# L298_driver.net
KiCad netlist of a schematic drawn in EAGLE
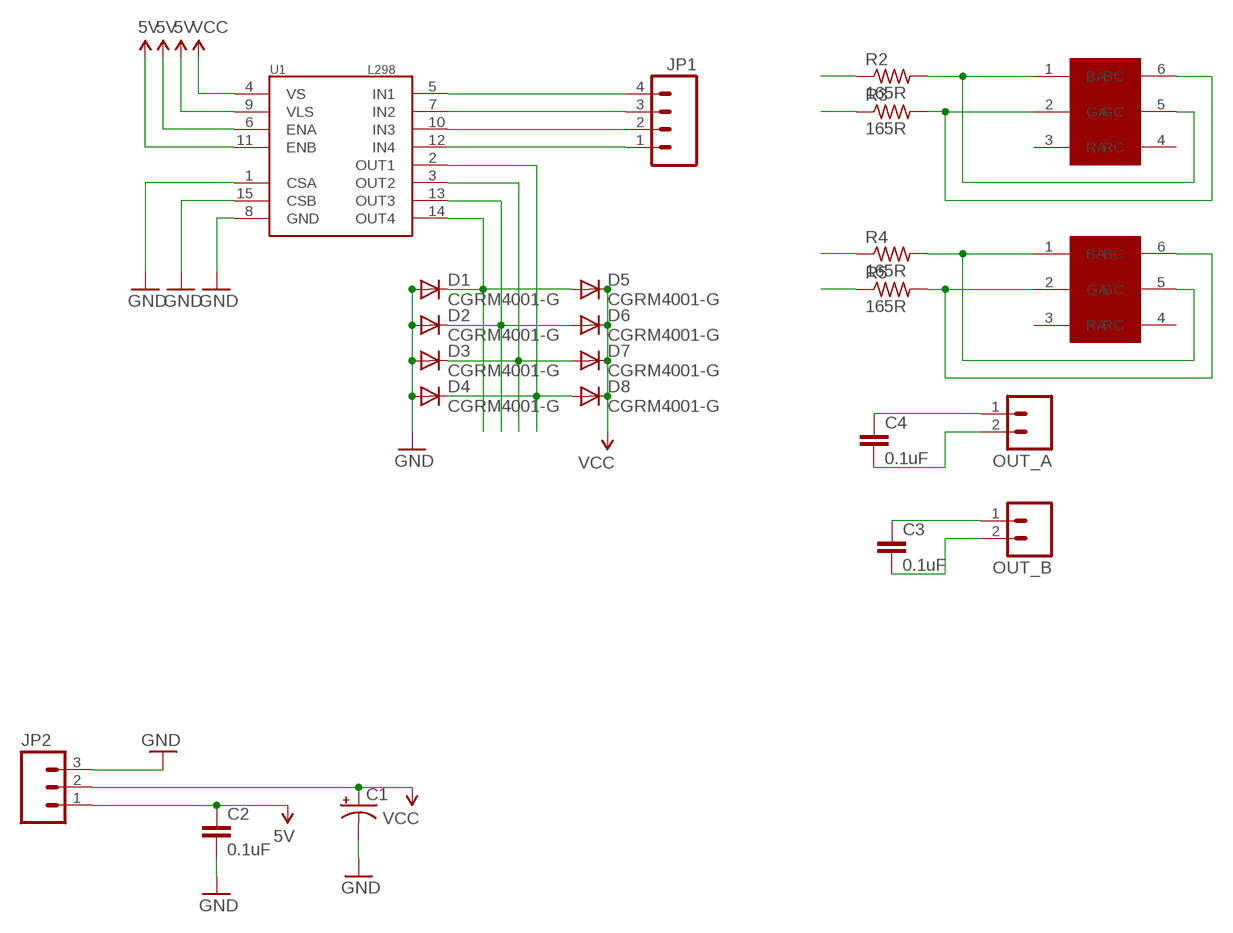
[diagram p0: schematic, sheet 1]

(export (version "E")
  (design (tool "Eeschema 10.0.6"))
  (components
    (comp (ref "C1")
      (value "CPOL-USTT5D11L")
      (footprint "eagle-import:TT5D11L")
      (libsource (lib "eagle-import") (part "CPOL-USTT5D11L"))
    )
    (comp (ref "C2")
      (value "0.1uF")
      (footprint "eagle-import:0402-CAP")
      (libsource (lib "eagle-import") (part "CAP0402-CAP"))
    )
    (comp (ref "C3")
      (value "0.1uF")
      (footprint "eagle-import:0402-CAP")
      (libsource (lib "eagle-import") (part "CAP0402-CAP"))
    )
    (comp (ref "C4")
      (value "0.1uF")
      (footprint "eagle-import:0402-CAP")
      (libsource (lib "eagle-import") (part "CAP0402-CAP"))
    )
    (comp (ref "D1")
      (value "CGRM4001-G")
      (footprint "eagle-import:SOD-123_MINI-SMA")
      (libsource (lib "eagle-import") (part "CGRM400-G1"))
    )
    (comp (ref "D2")
      (value "CGRM4001-G")
      (footprint "eagle-import:SOD-123_MINI-SMA")
      (libsource (lib "eagle-import") (part "CGRM400-G1"))
    )
    (comp (ref "D3")
      (value "CGRM4001-G")
      (footprint "eagle-import:SOD-123_MINI-SMA")
      (libsource (lib "eagle-import") (part "CGRM400-G1"))
    )
    (comp (ref "D4")
      (value "CGRM4001-G")
      (footprint "eagle-import:SOD-123_MINI-SMA")
      (libsource (lib "eagle-import") (part "CGRM400-G1"))
    )
    (comp (ref "D5")
      (value "CGRM4001-G")
      (footprint "eagle-import:SOD-123_MINI-SMA")
      (libsource (lib "eagle-import") (part "CGRM400-G1"))
    )
    (comp (ref "D6")
      (value "CGRM4001-G")
      (footprint "eagle-import:SOD-123_MINI-SMA")
      (libsource (lib "eagle-import") (part "CGRM400-G1"))
    )
    (comp (ref "D7")
      (value "CGRM4001-G")
      (footprint "eagle-import:SOD-123_MINI-SMA")
      (libsource (lib "eagle-import") (part "CGRM400-G1"))
    )
    (comp (ref "D8")
      (value "CGRM4001-G")
      (footprint "eagle-import:SOD-123_MINI-SMA")
      (libsource (lib "eagle-import") (part "CGRM400-G1"))
    )
    (comp (ref "JP1")
      (value "M04POLAR")
      (footprint "eagle-import:MOLEX-1X4")
      (libsource (lib "eagle-import") (part "M04POLAR"))
    )
    (comp (ref "JP2")
      (value "M03-SCREW-5MM")
      (footprint "eagle-import:SCREWTERMINAL-5MM-3")
      (libsource (lib "eagle-import") (part "M03-SCREW-5MM"))
    )
    (comp (ref "LED_A")
      (value "LRTB_R98G")
      (footprint "eagle-import:6-SMD")
      (libsource (lib "eagle-import") (part "LRTB_R98G"))
    )
    (comp (ref "LED_B")
      (value "LRTB_R98G")
      (footprint "eagle-import:6-SMD")
      (libsource (lib "eagle-import") (part "LRTB_R98G"))
    )
    (comp (ref "OUT_A")
      (value "M025MM")
      (footprint "eagle-import:SCREWTERMINAL-5MM-2")
      (libsource (lib "eagle-import") (part "M025MM"))
    )
    (comp (ref "OUT_B")
      (value "M025MM")
      (footprint "eagle-import:SCREWTERMINAL-5MM-2")
      (libsource (lib "eagle-import") (part "M025MM"))
    )
    (comp (ref "R2")
      (value "165R")
      (footprint "eagle-import:R0402")
      (libsource (lib "eagle-import") (part "R-US_R0402"))
    )
    (comp (ref "R3")
      (value "165R")
      (footprint "eagle-import:R0402")
      (libsource (lib "eagle-import") (part "R-US_R0402"))
    )
    (comp (ref "R4")
      (value "165R")
      (footprint "eagle-import:R0402")
      (libsource (lib "eagle-import") (part "R-US_R0402"))
    )
    (comp (ref "R5")
      (value "165R")
      (footprint "eagle-import:R0402")
      (libsource (lib "eagle-import") (part "R-US_R0402"))
    )
    (comp (ref "U1")
      (value "L298")
      (footprint "eagle-import:MULTIWATT15")
      (libsource (lib "eagle-import") (part "L298"))
    )
  )
  (nets
    (net (code "1") (name "/IN1") (class "Default")
      (node (ref "JP1") (pin "4") (pinfunction "4_4") (pintype "passive"))
      (node (ref "R2") (pin "1") (pinfunction "1_1") (pintype "passive"))
      (node (ref "U1") (pin "5") (pinfunction "IN1_5") (pintype "bidirectional"))
    )
    (net (code "2") (name "/IN2") (class "Default")
      (node (ref "JP1") (pin "3") (pinfunction "3_3") (pintype "passive"))
      (node (ref "R3") (pin "1") (pinfunction "1_1") (pintype "passive"))
      (node (ref "U1") (pin "7") (pinfunction "IN2_7") (pintype "bidirectional"))
    )
    (net (code "3") (name "/IN3") (class "Default")
      (node (ref "JP1") (pin "2") (pinfunction "2_2") (pintype "passive"))
      (node (ref "R4") (pin "1") (pinfunction "1_1") (pintype "passive"))
      (node (ref "U1") (pin "10") (pinfunction "IN3_10") (pintype "bidirectional"))
    )
    (net (code "4") (name "/IN4") (class "Default")
      (node (ref "JP1") (pin "1") (pinfunction "1_1") (pintype "passive"))
      (node (ref "R5") (pin "1") (pinfunction "1_1") (pintype "passive"))
      (node (ref "U1") (pin "12") (pinfunction "IN4_12") (pintype "bidirectional"))
    )
    (net (code "5") (name "/OUT1") (class "Default")
      (node (ref "C4") (pin "1") (pinfunction "1_1") (pintype "passive"))
      (node (ref "D4") (pin "C") (pinfunction "C_C") (pintype "passive"))
      (node (ref "D8") (pin "A") (pinfunction "A_A") (pintype "passive"))
      (node (ref "OUT_A") (pin "1") (pinfunction "1_1") (pintype "passive"))
      (node (ref "U1") (pin "2") (pinfunction "OUT1_2") (pintype "bidirectional"))
    )
    (net (code "6") (name "/OUT2") (class "Default")
      (node (ref "C4") (pin "2") (pinfunction "2_2") (pintype "passive"))
      (node (ref "D3") (pin "C") (pinfunction "C_C") (pintype "passive"))
      (node (ref "D7") (pin "A") (pinfunction "A_A") (pintype "passive"))
      (node (ref "OUT_A") (pin "2") (pinfunction "2_2") (pintype "passive"))
      (node (ref "U1") (pin "3") (pinfunction "OUT2_3") (pintype "bidirectional"))
    )
    (net (code "7") (name "/OUT3") (class "Default")
      (node (ref "C3") (pin "1") (pinfunction "1_1") (pintype "passive"))
      (node (ref "D2") (pin "C") (pinfunction "C_C") (pintype "passive"))
      (node (ref "D6") (pin "A") (pinfunction "A_A") (pintype "passive"))
      (node (ref "OUT_B") (pin "1") (pinfunction "1_1") (pintype "passive"))
      (node (ref "U1") (pin "13") (pinfunction "OUT3_13") (pintype "bidirectional"))
    )
    (net (code "8") (name "/OUT4") (class "Default")
      (node (ref "C3") (pin "2") (pinfunction "2_2") (pintype "passive"))
      (node (ref "D1") (pin "C") (pinfunction "C_C") (pintype "passive"))
      (node (ref "D5") (pin "A") (pinfunction "A_A") (pintype "passive"))
      (node (ref "OUT_B") (pin "2") (pinfunction "2_2") (pintype "passive"))
      (node (ref "U1") (pin "14") (pinfunction "OUT4_14") (pintype "bidirectional"))
    )
    (net (code "9") (name "5V") (class "Default")
      (node (ref "C2") (pin "1") (pinfunction "1_1") (pintype "passive"))
      (node (ref "JP2") (pin "1") (pinfunction "1_1") (pintype "passive"))
      (node (ref "U1") (pin "11") (pinfunction "ENB_11") (pintype "bidirectional"))
      (node (ref "U1") (pin "6") (pinfunction "ENA_6") (pintype "bidirectional"))
      (node (ref "U1") (pin "9") (pinfunction "VLS_9") (pintype "bidirectional"))
    )
    (net (code "10") (name "GND") (class "Default")
      (node (ref "C1") (pin "-") (pinfunction "-_-") (pintype "passive"))
      (node (ref "C2") (pin "2") (pinfunction "2_2") (pintype "passive"))
      (node (ref "D1") (pin "A") (pinfunction "A_A") (pintype "passive"))
      (node (ref "D2") (pin "A") (pinfunction "A_A") (pintype "passive"))
      (node (ref "D3") (pin "A") (pinfunction "A_A") (pintype "passive"))
      (node (ref "D4") (pin "A") (pinfunction "A_A") (pintype "passive"))
      (node (ref "JP2") (pin "3") (pinfunction "3_3") (pintype "passive"))
      (node (ref "U1") (pin "1") (pinfunction "CSA_1") (pintype "bidirectional"))
      (node (ref "U1") (pin "15") (pinfunction "CSB_15") (pintype "bidirectional"))
      (node (ref "U1") (pin "8") (pinfunction "GND_8") (pintype "bidirectional"))
    )
    (net (code "11") (name "Net-(LED_A-BA)") (class "Default")
      (node (ref "LED_A") (pin "1") (pinfunction "BA_1") (pintype "bidirectional"))
      (node (ref "LED_A") (pin "5") (pinfunction "GC_5") (pintype "bidirectional"))
      (node (ref "R2") (pin "2") (pinfunction "2_2") (pintype "passive"))
    )
    (net (code "12") (name "Net-(LED_A-BC)") (class "Default")
      (node (ref "LED_A") (pin "2") (pinfunction "GA_2") (pintype "bidirectional"))
      (node (ref "LED_A") (pin "6") (pinfunction "BC_6") (pintype "bidirectional"))
      (node (ref "R3") (pin "2") (pinfunction "2_2") (pintype "passive"))
    )
    (net (code "13") (name "Net-(LED_B-BA)") (class "Default")
      (node (ref "LED_B") (pin "1") (pinfunction "BA_1") (pintype "bidirectional"))
      (node (ref "LED_B") (pin "5") (pinfunction "GC_5") (pintype "bidirectional"))
      (node (ref "R4") (pin "2") (pinfunction "2_2") (pintype "passive"))
    )
    (net (code "14") (name "Net-(LED_B-BC)") (class "Default")
      (node (ref "LED_B") (pin "2") (pinfunction "GA_2") (pintype "bidirectional"))
      (node (ref "LED_B") (pin "6") (pinfunction "BC_6") (pintype "bidirectional"))
      (node (ref "R5") (pin "2") (pinfunction "2_2") (pintype "passive"))
    )
    (net (code "15") (name "VCC") (class "Default")
      (node (ref "C1") (pin "+") (pinfunction "+_+") (pintype "passive"))
      (node (ref "D5") (pin "C") (pinfunction "C_C") (pintype "passive"))
      (node (ref "D6") (pin "C") (pinfunction "C_C") (pintype "passive"))
      (node (ref "D7") (pin "C") (pinfunction "C_C") (pintype "passive"))
      (node (ref "D8") (pin "C") (pinfunction "C_C") (pintype "passive"))
      (node (ref "JP2") (pin "2") (pinfunction "2_2") (pintype "passive"))
      (node (ref "U1") (pin "4") (pinfunction "VS_4") (pintype "bidirectional"))
    )
    (net (code "16") (name "unconnected-(LED_A-RA-Pad3)") (class "Default")
      (node (ref "LED_A") (pin "3") (pinfunction "RA_3") (pintype "bidirectional"))
    )
    (net (code "17") (name "unconnected-(LED_A-RC-Pad4)") (class "Default")
      (node (ref "LED_A") (pin "4") (pinfunction "RC_4") (pintype "bidirectional"))
    )
    (net (code "18") (name "unconnected-(LED_B-RA-Pad3)") (class "Default")
      (node (ref "LED_B") (pin "3") (pinfunction "RA_3") (pintype "bidirectional"))
    )
    (net (code "19") (name "unconnected-(LED_B-RC-Pad4)") (class "Default")
      (node (ref "LED_B") (pin "4") (pinfunction "RC_4") (pintype "bidirectional"))
    )
  )
)
